# Debug.net
KiCad netlist of a schematic drawn in Altium Designer
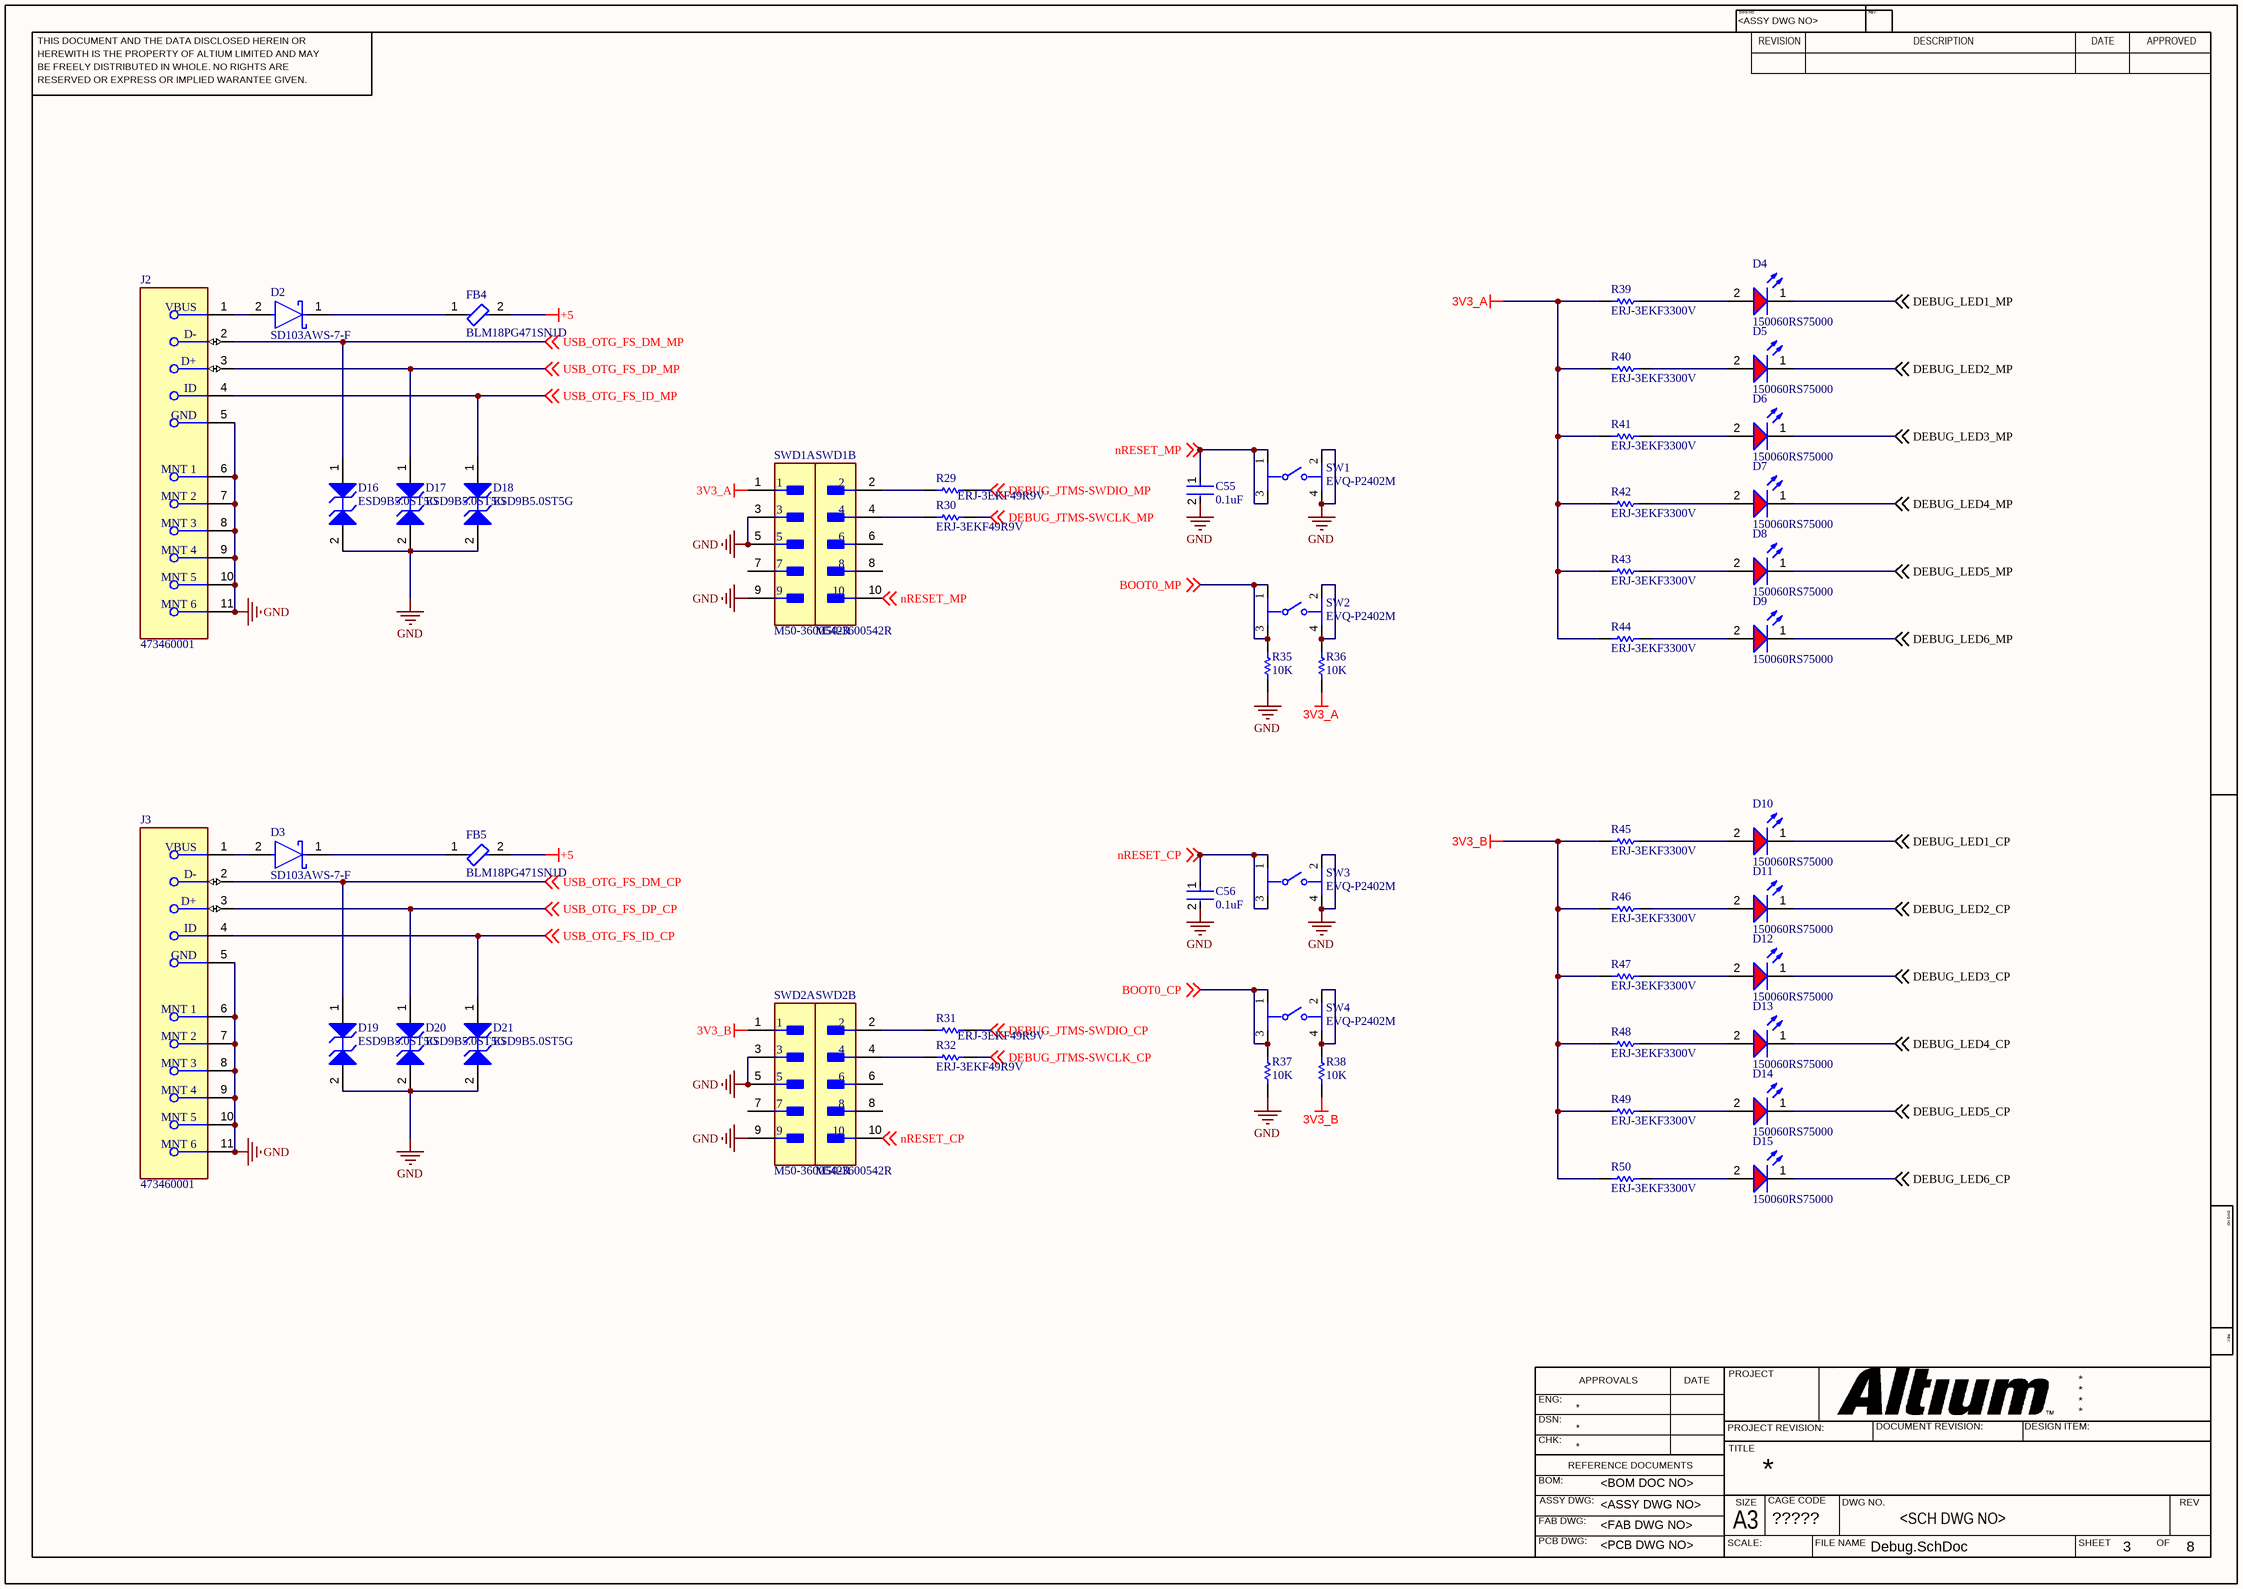
[diagram p0: Debug.SchDoc]

(export (version "E")
  (design (tool "Eeschema 10.0.6"))
  (components
    (comp (ref "C55")
      (value "0.1uF")
      (footprint "FP-C0603C-CF-MFG")
      (description "CAP CER 0.1UF 50V X7R 0603")
      (fields (field (name "TOLERANCE") "0.1") (field (name "MANUFACTURER") "KEMET"))
      (libsource (lib "Altium Content Vault") (part "b4654b650e69147ec39a6b967a45e02"))
    )
    (comp (ref "C56")
      (value "0.1uF")
      (footprint "FP-C0603C-CF-MFG")
      (description "CAP CER 0.1UF 50V X7R 0603")
      (fields (field (name "TOLERANCE") "0.1") (field (name "MANUFACTURER") "KEMET"))
      (libsource (lib "Altium Content Vault") (part "b4654b650e69147ec39a6b967a45e02"))
    )
    (comp (ref "D2")
      (value "SD103AWS-7-F")
      (footprint "FP-SOD323-MFG")
      (description "DIODE SCHOTTKY 40V 350MA SOD323")
      (fields
        (field (name "OCTOPART") "https://octopart.com/sd103aws-7-f-diodes+inc.-55389602")
        (field (name "MANUFACTURER") "Diodes Inc.")
      )
      (libsource (lib "Altium Content Vault") (part "1d6ec82d83fb6aee721767c19dac4b9"))
    )
    (comp (ref "D3")
      (value "SD103AWS-7-F")
      (footprint "FP-SOD323-MFG")
      (description "DIODE SCHOTTKY 40V 350MA SOD323")
      (fields
        (field (name "OCTOPART") "https://octopart.com/sd103aws-7-f-diodes+inc.-55389602")
        (field (name "MANUFACTURER") "Diodes Inc.")
      )
      (libsource (lib "Altium Content Vault") (part "1d6ec82d83fb6aee721767c19dac4b9"))
    )
    (comp (ref "D4")
      (value "150060RS75000")
      (footprint "WL-SMCW_0603_150060xx75000")
      (description "LED Low-Power Uni-Color Red 630nm 2V 2-Pin Chip 0603(1608Metric) T/R")
      (libsource (lib "Altium Content Vault") (part "LED_Red_2A-1K"))
    )
    (comp (ref "D5")
      (value "150060RS75000")
      (footprint "WL-SMCW_0603_150060xx75000")
      (description "LED Low-Power Uni-Color Red 630nm 2V 2-Pin Chip 0603(1608Metric) T/R")
      (libsource (lib "Altium Content Vault") (part "LED_Red_2A-1K"))
    )
    (comp (ref "D6")
      (value "150060RS75000")
      (footprint "WL-SMCW_0603_150060xx75000")
      (description "LED Low-Power Uni-Color Red 630nm 2V 2-Pin Chip 0603(1608Metric) T/R")
      (libsource (lib "Altium Content Vault") (part "LED_Red_2A-1K"))
    )
    (comp (ref "D7")
      (value "150060RS75000")
      (footprint "WL-SMCW_0603_150060xx75000")
      (description "LED Low-Power Uni-Color Red 630nm 2V 2-Pin Chip 0603(1608Metric) T/R")
      (libsource (lib "Altium Content Vault") (part "LED_Red_2A-1K"))
    )
    (comp (ref "D8")
      (value "150060RS75000")
      (footprint "WL-SMCW_0603_150060xx75000")
      (description "LED Low-Power Uni-Color Red 630nm 2V 2-Pin Chip 0603(1608Metric) T/R")
      (libsource (lib "Altium Content Vault") (part "LED_Red_2A-1K"))
    )
    (comp (ref "D9")
      (value "150060RS75000")
      (footprint "WL-SMCW_0603_150060xx75000")
      (description "LED Low-Power Uni-Color Red 630nm 2V 2-Pin Chip 0603(1608Metric) T/R")
      (libsource (lib "Altium Content Vault") (part "LED_Red_2A-1K"))
    )
    (comp (ref "D10")
      (value "150060RS75000")
      (footprint "WL-SMCW_0603_150060xx75000")
      (description "LED Low-Power Uni-Color Red 630nm 2V 2-Pin Chip 0603(1608Metric) T/R")
      (libsource (lib "Altium Content Vault") (part "LED_Red_2A-1K"))
    )
    (comp (ref "D11")
      (value "150060RS75000")
      (footprint "WL-SMCW_0603_150060xx75000")
      (description "LED Low-Power Uni-Color Red 630nm 2V 2-Pin Chip 0603(1608Metric) T/R")
      (libsource (lib "Altium Content Vault") (part "LED_Red_2A-1K"))
    )
    (comp (ref "D12")
      (value "150060RS75000")
      (footprint "WL-SMCW_0603_150060xx75000")
      (description "LED Low-Power Uni-Color Red 630nm 2V 2-Pin Chip 0603(1608Metric) T/R")
      (libsource (lib "Altium Content Vault") (part "LED_Red_2A-1K"))
    )
    (comp (ref "D13")
      (value "150060RS75000")
      (footprint "WL-SMCW_0603_150060xx75000")
      (description "LED Low-Power Uni-Color Red 630nm 2V 2-Pin Chip 0603(1608Metric) T/R")
      (libsource (lib "Altium Content Vault") (part "LED_Red_2A-1K"))
    )
    (comp (ref "D14")
      (value "150060RS75000")
      (footprint "WL-SMCW_0603_150060xx75000")
      (description "LED Low-Power Uni-Color Red 630nm 2V 2-Pin Chip 0603(1608Metric) T/R")
      (libsource (lib "Altium Content Vault") (part "LED_Red_2A-1K"))
    )
    (comp (ref "D15")
      (value "150060RS75000")
      (footprint "WL-SMCW_0603_150060xx75000")
      (description "LED Low-Power Uni-Color Red 630nm 2V 2-Pin Chip 0603(1608Metric) T/R")
      (libsource (lib "Altium Content Vault") (part "LED_Red_2A-1K"))
    )
    (comp (ref "D16")
      (value "ESD9B5.0ST5G")
      (footprint "ONSC-SOD-923-2-514AB-01_V")
      (fields (field (name "MANUFACTURER") "On Semiconductor"))
      (libsource (lib "Altium Content Vault") (part "ONSC-A1A2-2"))
    )
    (comp (ref "D17")
      (value "ESD9B5.0ST5G")
      (footprint "ONSC-SOD-923-2-514AB-01_V")
      (fields (field (name "MANUFACTURER") "On Semiconductor"))
      (libsource (lib "Altium Content Vault") (part "ONSC-A1A2-2"))
    )
    (comp (ref "D18")
      (value "ESD9B5.0ST5G")
      (footprint "ONSC-SOD-923-2-514AB-01_V")
      (fields (field (name "MANUFACTURER") "On Semiconductor"))
      (libsource (lib "Altium Content Vault") (part "ONSC-A1A2-2"))
    )
    (comp (ref "D19")
      (value "ESD9B5.0ST5G")
      (footprint "ONSC-SOD-923-2-514AB-01_V")
      (fields (field (name "MANUFACTURER") "On Semiconductor"))
      (libsource (lib "Altium Content Vault") (part "ONSC-A1A2-2"))
    )
    (comp (ref "D20")
      (value "ESD9B5.0ST5G")
      (footprint "ONSC-SOD-923-2-514AB-01_V")
      (fields (field (name "MANUFACTURER") "On Semiconductor"))
      (libsource (lib "Altium Content Vault") (part "ONSC-A1A2-2"))
    )
    (comp (ref "D21")
      (value "ESD9B5.0ST5G")
      (footprint "ONSC-SOD-923-2-514AB-01_V")
      (fields (field (name "MANUFACTURER") "On Semiconductor"))
      (libsource (lib "Altium Content Vault") (part "ONSC-A1A2-2"))
    )
    (comp (ref "FB4")
      (value "BLM18PG471SN1D")
      (footprint "FP-BLM18-0_15-t0_8-MFG")
      (description "Chip Ferrite Bead, 0603, 470Ω @ 100MHz, 0.2Ω, 25%, 1A")
      (fields (field (name "TOLERANCE") "25%"))
      (libsource (lib "Altium Content Vault") (part "5f30dd21d616792df468990f7003faa"))
    )
    (comp (ref "FB5")
      (value "BLM18PG471SN1D")
      (footprint "FP-BLM18-0_15-t0_8-MFG")
      (description "Chip Ferrite Bead, 0603, 470Ω @ 100MHz, 0.2Ω, 25%, 1A")
      (fields (field (name "TOLERANCE") "25%"))
      (libsource (lib "Altium Content Vault") (part "5f30dd21d616792df468990f7003faa"))
    )
    (comp (ref "J2")
      (value "473460001")
      (footprint "FP-473460001-MFG")
      (description "CONN RCPT USB2.0 MICRO B SMD R/A")
      (fields
        (field (name "OCTOPART") "https://octopart.com/47346-0001-molex-7164928")
        (field (name "MANUFACTURER") "Molex")
      )
      (libsource (lib "Altium Content Vault") (part "53ae1f1d9b557310b43ca686e5bb76a"))
    )
    (comp (ref "J3")
      (value "473460001")
      (footprint "FP-473460001-MFG")
      (description "CONN RCPT USB2.0 MICRO B SMD R/A")
      (fields
        (field (name "OCTOPART") "https://octopart.com/47346-0001-molex-7164928")
        (field (name "MANUFACTURER") "Molex")
      )
      (libsource (lib "Altium Content Vault") (part "53ae1f1d9b557310b43ca686e5bb76a"))
    )
    (comp (ref "R29")
      (value "ERJ-3EKF49R9V")
      (footprint "RESC1608X55X30ML15T15")
      (fields (field (name "MANUFACTURER") "Panasonic"))
      (libsource (lib "Altium Content Vault") (part "RES"))
    )
    (comp (ref "R30")
      (value "ERJ-3EKF49R9V")
      (footprint "RESC1608X55X30ML15T15")
      (fields (field (name "MANUFACTURER") "Panasonic"))
      (libsource (lib "Altium Content Vault") (part "RES"))
    )
    (comp (ref "R31")
      (value "ERJ-3EKF49R9V")
      (footprint "RESC1608X55X30ML15T15")
      (fields (field (name "MANUFACTURER") "Panasonic"))
      (libsource (lib "Altium Content Vault") (part "RES"))
    )
    (comp (ref "R32")
      (value "ERJ-3EKF49R9V")
      (footprint "RESC1608X55X30ML15T15")
      (fields (field (name "MANUFACTURER") "Panasonic"))
      (libsource (lib "Altium Content Vault") (part "RES"))
    )
    (comp (ref "R35")
      (value "10K")
      (footprint "RESC1609X55X30LL15T15")
      (description "Chip Resistor, 10 KOhm, +/- 1%, 0.1 W, -55 to 155 degC, 0603 (1608 Metric), RoHS, Tape and Reel")
      (fields (field (name "TOLERANCE") "1%") (field (name "MANUFACTURER") "Panasonic"))
      (libsource (lib "Altium Content Vault") (part "RES-2"))
    )
    (comp (ref "R36")
      (value "10K")
      (footprint "RESC1609X55X30LL15T15")
      (description "Chip Resistor, 10 KOhm, +/- 1%, 0.1 W, -55 to 155 degC, 0603 (1608 Metric), RoHS, Tape and Reel")
      (fields (field (name "TOLERANCE") "1%") (field (name "MANUFACTURER") "Panasonic"))
      (libsource (lib "Altium Content Vault") (part "RES-2"))
    )
    (comp (ref "R37")
      (value "10K")
      (footprint "RESC1609X55X30LL15T15")
      (description "Chip Resistor, 10 KOhm, +/- 1%, 0.1 W, -55 to 155 degC, 0603 (1608 Metric), RoHS, Tape and Reel")
      (fields (field (name "TOLERANCE") "1%") (field (name "MANUFACTURER") "Panasonic"))
      (libsource (lib "Altium Content Vault") (part "RES-2"))
    )
    (comp (ref "R38")
      (value "10K")
      (footprint "RESC1609X55X30LL15T15")
      (description "Chip Resistor, 10 KOhm, +/- 1%, 0.1 W, -55 to 155 degC, 0603 (1608 Metric), RoHS, Tape and Reel")
      (fields (field (name "TOLERANCE") "1%") (field (name "MANUFACTURER") "Panasonic"))
      (libsource (lib "Altium Content Vault") (part "RES-2"))
    )
    (comp (ref "R39")
      (value "ERJ-3EKF3300V")
      (footprint "RESC1608X55X30LL15T15")
      (description "Chip Resistor, 330 Ohm, +/- 1%, 0.1 W, -55 to 155 degC, 0603 (1608 Metric), RoHS, Tape and Reel")
      (libsource (lib "Altium Content Vault") (part "RES-2"))
    )
    (comp (ref "R40")
      (value "ERJ-3EKF3300V")
      (footprint "RESC1608X55X30LL15T15")
      (description "Chip Resistor, 330 Ohm, +/- 1%, 0.1 W, -55 to 155 degC, 0603 (1608 Metric), RoHS, Tape and Reel")
      (libsource (lib "Altium Content Vault") (part "RES-2"))
    )
    (comp (ref "R41")
      (value "ERJ-3EKF3300V")
      (footprint "RESC1608X55X30LL15T15")
      (description "Chip Resistor, 330 Ohm, +/- 1%, 0.1 W, -55 to 155 degC, 0603 (1608 Metric), RoHS, Tape and Reel")
      (libsource (lib "Altium Content Vault") (part "RES-2"))
    )
    (comp (ref "R42")
      (value "ERJ-3EKF3300V")
      (footprint "RESC1608X55X30LL15T15")
      (description "Chip Resistor, 330 Ohm, +/- 1%, 0.1 W, -55 to 155 degC, 0603 (1608 Metric), RoHS, Tape and Reel")
      (libsource (lib "Altium Content Vault") (part "RES-2"))
    )
    (comp (ref "R43")
      (value "ERJ-3EKF3300V")
      (footprint "RESC1608X55X30LL15T15")
      (description "Chip Resistor, 330 Ohm, +/- 1%, 0.1 W, -55 to 155 degC, 0603 (1608 Metric), RoHS, Tape and Reel")
      (libsource (lib "Altium Content Vault") (part "RES-2"))
    )
    (comp (ref "R44")
      (value "ERJ-3EKF3300V")
      (footprint "RESC1608X55X30LL15T15")
      (description "Chip Resistor, 330 Ohm, +/- 1%, 0.1 W, -55 to 155 degC, 0603 (1608 Metric), RoHS, Tape and Reel")
      (libsource (lib "Altium Content Vault") (part "RES-2"))
    )
    (comp (ref "R45")
      (value "ERJ-3EKF3300V")
      (footprint "RESC1608X55X30LL15T15")
      (description "Chip Resistor, 330 Ohm, +/- 1%, 0.1 W, -55 to 155 degC, 0603 (1608 Metric), RoHS, Tape and Reel")
      (libsource (lib "Altium Content Vault") (part "RES-2"))
    )
    (comp (ref "R46")
      (value "ERJ-3EKF3300V")
      (footprint "RESC1608X55X30LL15T15")
      (description "Chip Resistor, 330 Ohm, +/- 1%, 0.1 W, -55 to 155 degC, 0603 (1608 Metric), RoHS, Tape and Reel")
      (libsource (lib "Altium Content Vault") (part "RES-2"))
    )
    (comp (ref "R47")
      (value "ERJ-3EKF3300V")
      (footprint "RESC1608X55X30LL15T15")
      (description "Chip Resistor, 330 Ohm, +/- 1%, 0.1 W, -55 to 155 degC, 0603 (1608 Metric), RoHS, Tape and Reel")
      (libsource (lib "Altium Content Vault") (part "RES-2"))
    )
    (comp (ref "R48")
      (value "ERJ-3EKF3300V")
      (footprint "RESC1608X55X30LL15T15")
      (description "Chip Resistor, 330 Ohm, +/- 1%, 0.1 W, -55 to 155 degC, 0603 (1608 Metric), RoHS, Tape and Reel")
      (libsource (lib "Altium Content Vault") (part "RES-2"))
    )
    (comp (ref "R49")
      (value "ERJ-3EKF3300V")
      (footprint "RESC1608X55X30LL15T15")
      (description "Chip Resistor, 330 Ohm, +/- 1%, 0.1 W, -55 to 155 degC, 0603 (1608 Metric), RoHS, Tape and Reel")
      (libsource (lib "Altium Content Vault") (part "RES-2"))
    )
    (comp (ref "R50")
      (value "ERJ-3EKF3300V")
      (footprint "RESC1608X55X30LL15T15")
      (description "Chip Resistor, 330 Ohm, +/- 1%, 0.1 W, -55 to 155 degC, 0603 (1608 Metric), RoHS, Tape and Reel")
      (libsource (lib "Altium Content Vault") (part "RES-2"))
    )
    (comp (ref "SW1")
      (value "EVQ-P2402M")
      (footprint "FP-EVQ-P2402M-MFG")
      (description "SWITCH TACTILE SPST-NO 0.02A 15V")
      (libsource (lib "Altium Content Vault") (part "cb67941ecbda1860b707deecc235d4d"))
    )
    (comp (ref "SW2")
      (value "EVQ-P2402M")
      (footprint "FP-EVQ-P2402M-MFG")
      (description "SWITCH TACTILE SPST-NO 0.02A 15V")
      (libsource (lib "Altium Content Vault") (part "cb67941ecbda1860b707deecc235d4d"))
    )
    (comp (ref "SW3")
      (value "EVQ-P2402M")
      (footprint "FP-EVQ-P2402M-MFG")
      (description "SWITCH TACTILE SPST-NO 0.02A 15V")
      (libsource (lib "Altium Content Vault") (part "cb67941ecbda1860b707deecc235d4d"))
    )
    (comp (ref "SW4")
      (value "EVQ-P2402M")
      (footprint "FP-EVQ-P2402M-MFG")
      (description "SWITCH TACTILE SPST-NO 0.02A 15V")
      (libsource (lib "Altium Content Vault") (part "cb67941ecbda1860b707deecc235d4d"))
    )
    (comp (ref "SWD1")
      (value "M50-3600542R")
      (footprint "FP-M50-3600542R-MFG")
      (description "CONN HEADER SMD 10POS 1.27MM")
      (libsource (lib "") (part "544f42128f4185dcb88ce1ce9bf1982_1"))
    )
    (comp (ref "SWD2")
      (value "M50-3600542R")
      (footprint "FP-M50-3600542R-MFG")
      (description "CONN HEADER SMD 10POS 1.27MM")
      (libsource (lib "") (part "544f42128f4185dcb88ce1ce9bf1982_1"))
    )
  )
  (nets
    (net (code "1") (name "+5") (class "Default")
      (node (ref "FB4") (pin "2") (pinfunction "2_2") (pintype "passive"))
      (node (ref "FB5") (pin "2") (pinfunction "2_2") (pintype "passive"))
    )
    (net (code "2") (name "3V3_A") (class "Default")
      (node (ref "R36") (pin "1") (pinfunction "1_1") (pintype "passive"))
      (node (ref "R39") (pin "1") (pinfunction "1_1") (pintype "passive"))
      (node (ref "R40") (pin "1") (pinfunction "1_1") (pintype "passive"))
      (node (ref "R41") (pin "1") (pinfunction "1_1") (pintype "passive"))
      (node (ref "R42") (pin "1") (pinfunction "1_1") (pintype "passive"))
      (node (ref "R43") (pin "1") (pinfunction "1_1") (pintype "passive"))
      (node (ref "R44") (pin "1") (pinfunction "1_1") (pintype "passive"))
      (node (ref "SWD1") (pin "1") (pinfunction "1_1") (pintype "passive"))
    )
    (net (code "3") (name "3V3_B") (class "Default")
      (node (ref "R38") (pin "1") (pinfunction "1_1") (pintype "passive"))
      (node (ref "R45") (pin "1") (pinfunction "1_1") (pintype "passive"))
      (node (ref "R46") (pin "1") (pinfunction "1_1") (pintype "passive"))
      (node (ref "R47") (pin "1") (pinfunction "1_1") (pintype "passive"))
      (node (ref "R48") (pin "1") (pinfunction "1_1") (pintype "passive"))
      (node (ref "R49") (pin "1") (pinfunction "1_1") (pintype "passive"))
      (node (ref "R50") (pin "1") (pinfunction "1_1") (pintype "passive"))
      (node (ref "SWD2") (pin "1") (pinfunction "1_1") (pintype "passive"))
    )
    (net (code "4") (name "BOOT0_CP") (class "Default")
      (node (ref "R37") (pin "2") (pinfunction "2_2") (pintype "passive"))
      (node (ref "SW4") (pin "1") (pinfunction "1_1") (pintype "passive"))
      (node (ref "SW4") (pin "3") (pinfunction "3_3") (pintype "passive"))
    )
    (net (code "5") (name "BOOT0_MP") (class "Default")
      (node (ref "R35") (pin "2") (pinfunction "2_2") (pintype "passive"))
      (node (ref "SW2") (pin "1") (pinfunction "1_1") (pintype "passive"))
      (node (ref "SW2") (pin "3") (pinfunction "3_3") (pintype "passive"))
    )
    (net (code "6") (name "DEBUG_JTMS-SWCLK_CP") (class "Default")
      (node (ref "R32") (pin "2") (pinfunction "2_2") (pintype "passive"))
    )
    (net (code "7") (name "DEBUG_JTMS-SWCLK_MP") (class "Default")
      (node (ref "R30") (pin "2") (pinfunction "2_2") (pintype "passive"))
    )
    (net (code "8") (name "DEBUG_JTMS-SWDIO_CP") (class "Default")
      (node (ref "R31") (pin "2") (pinfunction "2_2") (pintype "passive"))
    )
    (net (code "9") (name "DEBUG_JTMS-SWDIO_MP") (class "Default")
      (node (ref "R29") (pin "2") (pinfunction "2_2") (pintype "passive"))
    )
    (net (code "10") (name "DEBUG_LED1_CP") (class "Default")
      (node (ref "D10") (pin "1") (pinfunction "K_1") (pintype "passive"))
    )
    (net (code "11") (name "DEBUG_LED1_MP") (class "Default")
      (node (ref "D4") (pin "1") (pinfunction "K_1") (pintype "passive"))
    )
    (net (code "12") (name "DEBUG_LED2_CP") (class "Default")
      (node (ref "D11") (pin "1") (pinfunction "K_1") (pintype "passive"))
    )
    (net (code "13") (name "DEBUG_LED2_MP") (class "Default")
      (node (ref "D5") (pin "1") (pinfunction "K_1") (pintype "passive"))
    )
    (net (code "14") (name "DEBUG_LED3_CP") (class "Default")
      (node (ref "D12") (pin "1") (pinfunction "K_1") (pintype "passive"))
    )
    (net (code "15") (name "DEBUG_LED3_MP") (class "Default")
      (node (ref "D6") (pin "1") (pinfunction "K_1") (pintype "passive"))
    )
    (net (code "16") (name "DEBUG_LED4_CP") (class "Default")
      (node (ref "D13") (pin "1") (pinfunction "K_1") (pintype "passive"))
    )
    (net (code "17") (name "DEBUG_LED4_MP") (class "Default")
      (node (ref "D7") (pin "1") (pinfunction "K_1") (pintype "passive"))
    )
    (net (code "18") (name "DEBUG_LED5_CP") (class "Default")
      (node (ref "D14") (pin "1") (pinfunction "K_1") (pintype "passive"))
    )
    (net (code "19") (name "DEBUG_LED5_MP") (class "Default")
      (node (ref "D8") (pin "1") (pinfunction "K_1") (pintype "passive"))
    )
    (net (code "20") (name "DEBUG_LED6_CP") (class "Default")
      (node (ref "D15") (pin "1") (pinfunction "K_1") (pintype "passive"))
    )
    (net (code "21") (name "DEBUG_LED6_MP") (class "Default")
      (node (ref "D9") (pin "1") (pinfunction "K_1") (pintype "passive"))
    )
    (net (code "22") (name "GND") (class "Default")
      (node (ref "C55") (pin "2") (pinfunction "2_2") (pintype "passive"))
      (node (ref "C56") (pin "2") (pinfunction "2_2") (pintype "passive"))
      (node (ref "D16") (pin "2") (pinfunction "A2_2") (pintype "passive"))
      (node (ref "D17") (pin "2") (pinfunction "A2_2") (pintype "passive"))
      (node (ref "D18") (pin "2") (pinfunction "A2_2") (pintype "passive"))
      (node (ref "D19") (pin "2") (pinfunction "A2_2") (pintype "passive"))
      (node (ref "D20") (pin "2") (pinfunction "A2_2") (pintype "passive"))
      (node (ref "D21") (pin "2") (pinfunction "A2_2") (pintype "passive"))
      (node (ref "J2") (pin "10") (pinfunction "MNT_5_10") (pintype "passive"))
      (node (ref "J2") (pin "11") (pinfunction "MNT_6_11") (pintype "passive"))
      (node (ref "J2") (pin "5") (pinfunction "GND_5") (pintype "power_in"))
      (node (ref "J2") (pin "6") (pinfunction "MNT_1_6") (pintype "passive"))
      (node (ref "J2") (pin "7") (pinfunction "MNT_2_7") (pintype "passive"))
      (node (ref "J2") (pin "8") (pinfunction "MNT_3_8") (pintype "passive"))
      (node (ref "J2") (pin "9") (pinfunction "MNT_4_9") (pintype "passive"))
      (node (ref "J3") (pin "10") (pinfunction "MNT_5_10") (pintype "passive"))
      (node (ref "J3") (pin "11") (pinfunction "MNT_6_11") (pintype "passive"))
      (node (ref "J3") (pin "5") (pinfunction "GND_5") (pintype "power_in"))
      (node (ref "J3") (pin "6") (pinfunction "MNT_1_6") (pintype "passive"))
      (node (ref "J3") (pin "7") (pinfunction "MNT_2_7") (pintype "passive"))
      (node (ref "J3") (pin "8") (pinfunction "MNT_3_8") (pintype "passive"))
      (node (ref "J3") (pin "9") (pinfunction "MNT_4_9") (pintype "passive"))
      (node (ref "R35") (pin "1") (pinfunction "1_1") (pintype "passive"))
      (node (ref "R37") (pin "1") (pinfunction "1_1") (pintype "passive"))
      (node (ref "SW1") (pin "2") (pinfunction "2_2") (pintype "passive"))
      (node (ref "SW1") (pin "4") (pinfunction "4_4") (pintype "passive"))
      (node (ref "SW3") (pin "2") (pinfunction "2_2") (pintype "passive"))
      (node (ref "SW3") (pin "4") (pinfunction "4_4") (pintype "passive"))
      (node (ref "SWD1") (pin "3") (pinfunction "3_3") (pintype "passive"))
      (node (ref "SWD1") (pin "5") (pinfunction "5_5") (pintype "passive"))
      (node (ref "SWD1") (pin "9") (pinfunction "9_9") (pintype "passive"))
      (node (ref "SWD2") (pin "3") (pinfunction "3_3") (pintype "passive"))
      (node (ref "SWD2") (pin "5") (pinfunction "5_5") (pintype "passive"))
      (node (ref "SWD2") (pin "9") (pinfunction "9_9") (pintype "passive"))
    )
    (net (code "23") (name "Net-(D2-A)") (class "Default")
      (node (ref "D2") (pin "2") (pinfunction "A_2") (pintype "passive"))
      (node (ref "J2") (pin "1") (pinfunction "VBUS_1") (pintype "power_in"))
    )
    (net (code "24") (name "Net-(D2-C)") (class "Default")
      (node (ref "D2") (pin "1") (pinfunction "C_1") (pintype "passive"))
      (node (ref "FB4") (pin "1") (pinfunction "1_1") (pintype "passive"))
    )
    (net (code "25") (name "Net-(D3-A)") (class "Default")
      (node (ref "D3") (pin "2") (pinfunction "A_2") (pintype "passive"))
      (node (ref "J3") (pin "1") (pinfunction "VBUS_1") (pintype "power_in"))
    )
    (net (code "26") (name "Net-(D3-C)") (class "Default")
      (node (ref "D3") (pin "1") (pinfunction "C_1") (pintype "passive"))
      (node (ref "FB5") (pin "1") (pinfunction "1_1") (pintype "passive"))
    )
    (net (code "27") (name "Net-(D4-A)") (class "Default")
      (node (ref "D4") (pin "2") (pinfunction "A_2") (pintype "passive"))
      (node (ref "R39") (pin "2") (pinfunction "2_2") (pintype "passive"))
    )
    (net (code "28") (name "Net-(D5-A)") (class "Default")
      (node (ref "D5") (pin "2") (pinfunction "A_2") (pintype "passive"))
      (node (ref "R40") (pin "2") (pinfunction "2_2") (pintype "passive"))
    )
    (net (code "29") (name "Net-(D6-A)") (class "Default")
      (node (ref "D6") (pin "2") (pinfunction "A_2") (pintype "passive"))
      (node (ref "R41") (pin "2") (pinfunction "2_2") (pintype "passive"))
    )
    (net (code "30") (name "Net-(D7-A)") (class "Default")
      (node (ref "D7") (pin "2") (pinfunction "A_2") (pintype "passive"))
      (node (ref "R42") (pin "2") (pinfunction "2_2") (pintype "passive"))
    )
    (net (code "31") (name "Net-(D8-A)") (class "Default")
      (node (ref "D8") (pin "2") (pinfunction "A_2") (pintype "passive"))
      (node (ref "R43") (pin "2") (pinfunction "2_2") (pintype "passive"))
    )
    (net (code "32") (name "Net-(D9-A)") (class "Default")
      (node (ref "D9") (pin "2") (pinfunction "A_2") (pintype "passive"))
      (node (ref "R44") (pin "2") (pinfunction "2_2") (pintype "passive"))
    )
    (net (code "33") (name "Net-(D10-A)") (class "Default")
      (node (ref "D10") (pin "2") (pinfunction "A_2") (pintype "passive"))
      (node (ref "R45") (pin "2") (pinfunction "2_2") (pintype "passive"))
    )
    (net (code "34") (name "Net-(D11-A)") (class "Default")
      (node (ref "D11") (pin "2") (pinfunction "A_2") (pintype "passive"))
      (node (ref "R46") (pin "2") (pinfunction "2_2") (pintype "passive"))
    )
    (net (code "35") (name "Net-(D12-A)") (class "Default")
      (node (ref "D12") (pin "2") (pinfunction "A_2") (pintype "passive"))
      (node (ref "R47") (pin "2") (pinfunction "2_2") (pintype "passive"))
    )
    (net (code "36") (name "Net-(D13-A)") (class "Default")
      (node (ref "D13") (pin "2") (pinfunction "A_2") (pintype "passive"))
      (node (ref "R48") (pin "2") (pinfunction "2_2") (pintype "passive"))
    )
    (net (code "37") (name "Net-(D14-A)") (class "Default")
      (node (ref "D14") (pin "2") (pinfunction "A_2") (pintype "passive"))
      (node (ref "R49") (pin "2") (pinfunction "2_2") (pintype "passive"))
    )
    (net (code "38") (name "Net-(D15-A)") (class "Default")
      (node (ref "D15") (pin "2") (pinfunction "A_2") (pintype "passive"))
      (node (ref "R50") (pin "2") (pinfunction "2_2") (pintype "passive"))
    )
    (net (code "39") (name "Net-(R29-Pad1)") (class "Default")
      (node (ref "R29") (pin "1") (pinfunction "1_1") (pintype "passive"))
      (node (ref "SWD1") (pin "2") (pinfunction "2_2") (pintype "passive"))
    )
    (net (code "40") (name "Net-(R30-Pad1)") (class "Default")
      (node (ref "R30") (pin "1") (pinfunction "1_1") (pintype "passive"))
      (node (ref "SWD1") (pin "4") (pinfunction "4_4") (pintype "passive"))
    )
    (net (code "41") (name "Net-(R31-Pad1)") (class "Default")
      (node (ref "R31") (pin "1") (pinfunction "1_1") (pintype "passive"))
      (node (ref "SWD2") (pin "2") (pinfunction "2_2") (pintype "passive"))
    )
    (net (code "42") (name "Net-(R32-Pad1)") (class "Default")
      (node (ref "R32") (pin "1") (pinfunction "1_1") (pintype "passive"))
      (node (ref "SWD2") (pin "4") (pinfunction "4_4") (pintype "passive"))
    )
    (net (code "43") (name "Net-(R36-Pad2)") (class "Default")
      (node (ref "R36") (pin "2") (pinfunction "2_2") (pintype "passive"))
      (node (ref "SW2") (pin "2") (pinfunction "2_2") (pintype "passive"))
      (node (ref "SW2") (pin "4") (pinfunction "4_4") (pintype "passive"))
    )
    (net (code "44") (name "Net-(R38-Pad2)") (class "Default")
      (node (ref "R38") (pin "2") (pinfunction "2_2") (pintype "passive"))
      (node (ref "SW4") (pin "2") (pinfunction "2_2") (pintype "passive"))
      (node (ref "SW4") (pin "4") (pinfunction "4_4") (pintype "passive"))
    )
    (net (code "45") (name "USB_OTG_FS_DM_CP") (class "Default")
      (node (ref "D19") (pin "1") (pinfunction "A1_1") (pintype "passive"))
      (node (ref "J3") (pin "2") (pinfunction "D-_2") (pintype "bidirectional"))
    )
    (net (code "46") (name "USB_OTG_FS_DM_MP") (class "Default")
      (node (ref "D16") (pin "1") (pinfunction "A1_1") (pintype "passive"))
      (node (ref "J2") (pin "2") (pinfunction "D-_2") (pintype "bidirectional"))
    )
    (net (code "47") (name "USB_OTG_FS_DP_CP") (class "Default")
      (node (ref "D20") (pin "1") (pinfunction "A1_1") (pintype "passive"))
      (node (ref "J3") (pin "3") (pinfunction "D+_3") (pintype "bidirectional"))
    )
    (net (code "48") (name "USB_OTG_FS_DP_MP") (class "Default")
      (node (ref "D17") (pin "1") (pinfunction "A1_1") (pintype "passive"))
      (node (ref "J2") (pin "3") (pinfunction "D+_3") (pintype "bidirectional"))
    )
    (net (code "49") (name "USB_OTG_FS_ID_CP") (class "Default")
      (node (ref "D21") (pin "1") (pinfunction "A1_1") (pintype "passive"))
      (node (ref "J3") (pin "4") (pinfunction "ID_4") (pintype "passive"))
    )
    (net (code "50") (name "USB_OTG_FS_ID_MP") (class "Default")
      (node (ref "D18") (pin "1") (pinfunction "A1_1") (pintype "passive"))
      (node (ref "J2") (pin "4") (pinfunction "ID_4") (pintype "passive"))
    )
    (net (code "51") (name "nRESET_CP") (class "Default")
      (node (ref "C56") (pin "1") (pinfunction "1_1") (pintype "passive"))
      (node (ref "SW3") (pin "1") (pinfunction "1_1") (pintype "passive"))
      (node (ref "SW3") (pin "3") (pinfunction "3_3") (pintype "passive"))
      (node (ref "SWD2") (pin "10") (pinfunction "10_10") (pintype "passive"))
    )
    (net (code "52") (name "nRESET_MP") (class "Default")
      (node (ref "C55") (pin "1") (pinfunction "1_1") (pintype "passive"))
      (node (ref "SW1") (pin "1") (pinfunction "1_1") (pintype "passive"))
      (node (ref "SW1") (pin "3") (pinfunction "3_3") (pintype "passive"))
      (node (ref "SWD1") (pin "10") (pinfunction "10_10") (pintype "passive"))
    )
    (net (code "53") (name "unconnected-(SWD1-Pad6)") (class "Default")
      (node (ref "SWD1") (pin "6") (pinfunction "6_6") (pintype "passive"))
    )
    (net (code "54") (name "unconnected-(SWD1-Pad7)") (class "Default")
      (node (ref "SWD1") (pin "7") (pinfunction "7_7") (pintype "passive"))
    )
    (net (code "55") (name "unconnected-(SWD1-Pad8)") (class "Default")
      (node (ref "SWD1") (pin "8") (pinfunction "8_8") (pintype "passive"))
    )
    (net (code "56") (name "unconnected-(SWD2-Pad6)") (class "Default")
      (node (ref "SWD2") (pin "6") (pinfunction "6_6") (pintype "passive"))
    )
    (net (code "57") (name "unconnected-(SWD2-Pad7)") (class "Default")
      (node (ref "SWD2") (pin "7") (pinfunction "7_7") (pintype "passive"))
    )
    (net (code "58") (name "unconnected-(SWD2-Pad8)") (class "Default")
      (node (ref "SWD2") (pin "8") (pinfunction "8_8") (pintype "passive"))
    )
  )
)
